# stm32f4stampV1_2.net
KiCad netlist of a schematic drawn in EAGLE
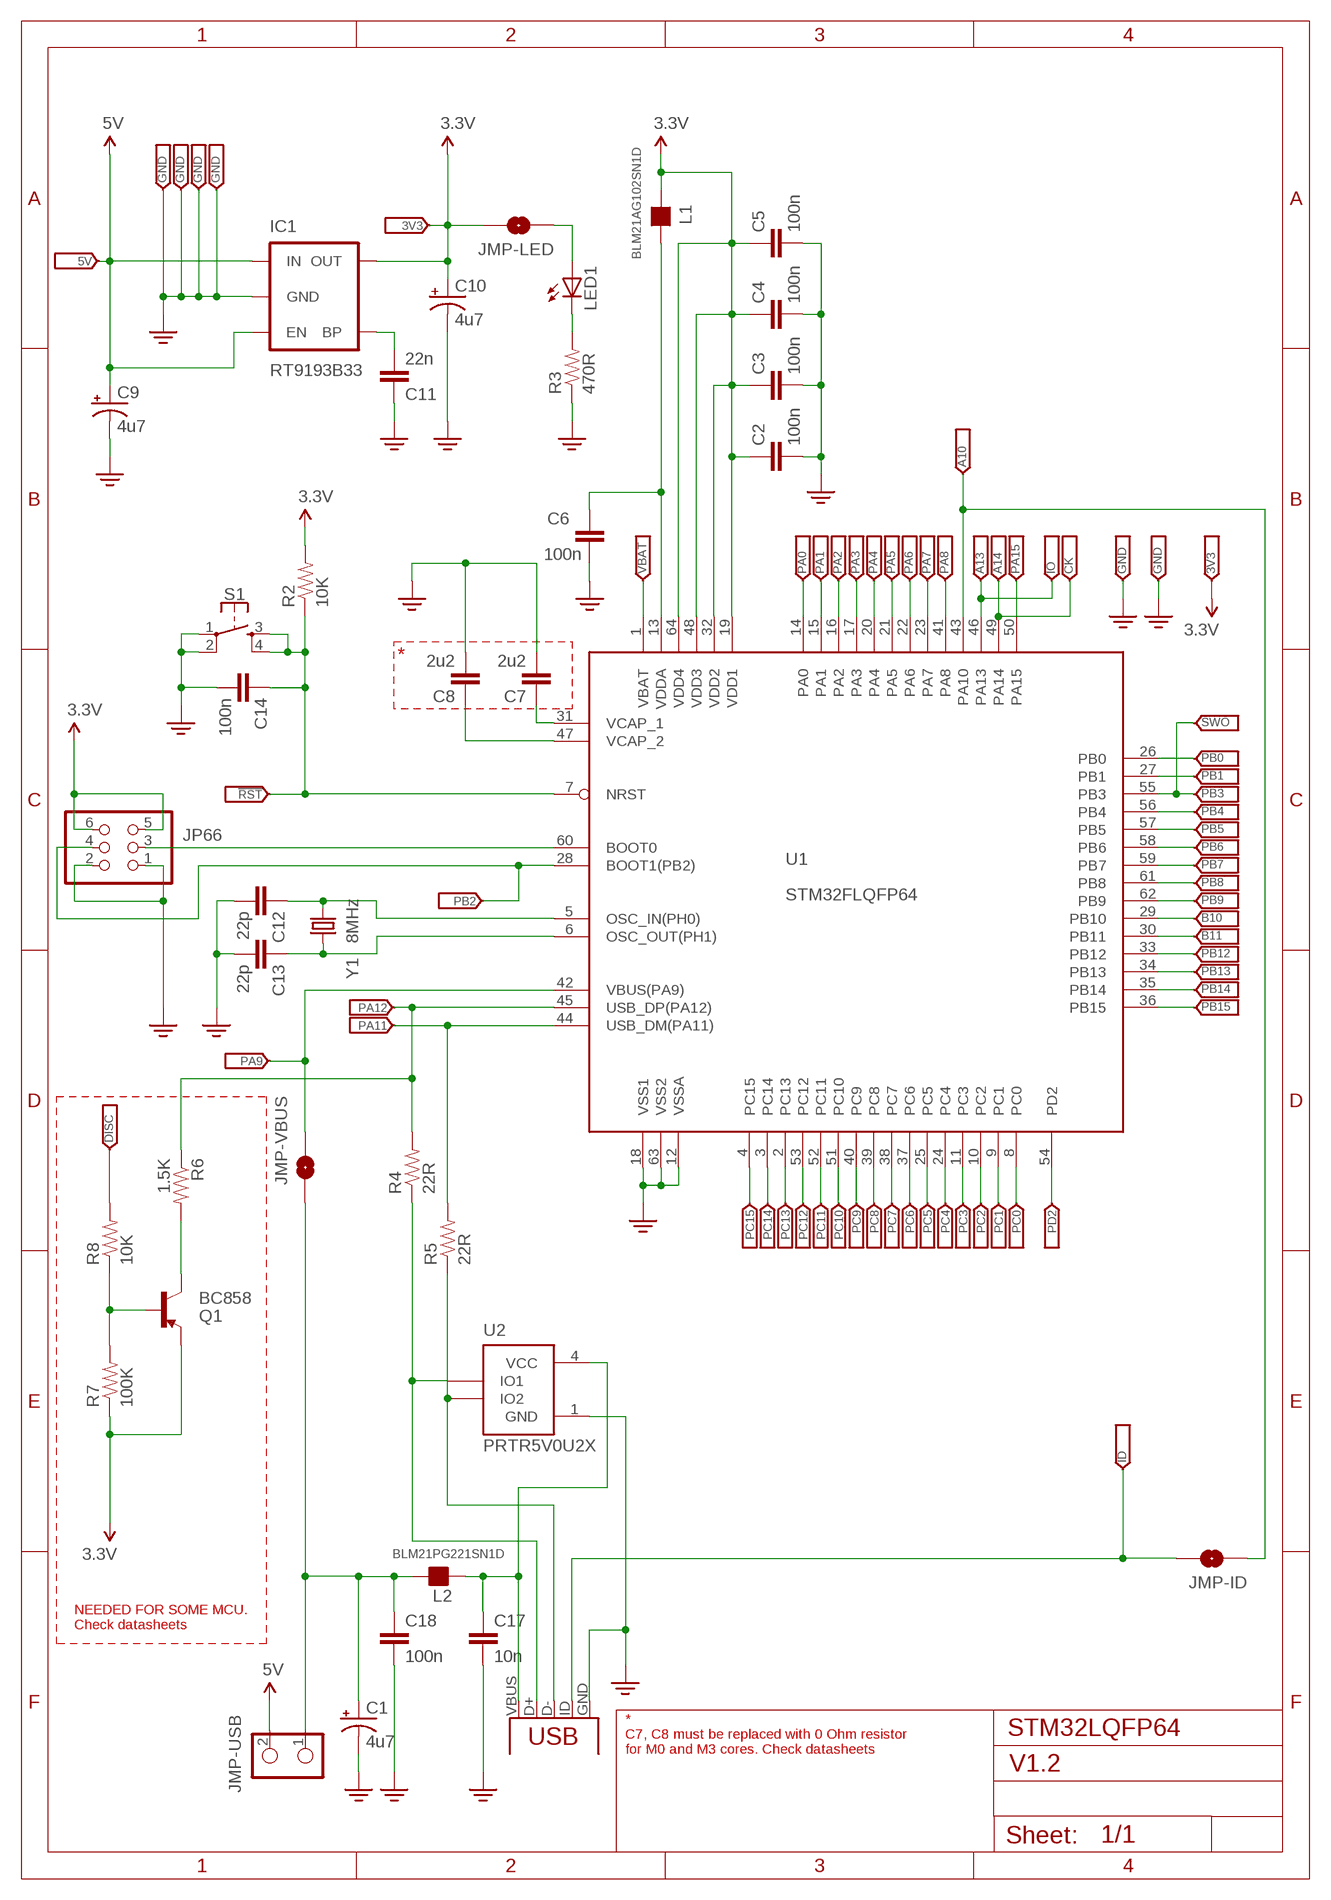
[diagram p0: schematic, sheet 1]

(export (version "E")
  (design (tool "Eeschema 10.0.6"))
  (components
    (comp (ref "C1")
      (value "4u7")
      (footprint "eagle-import:EIA3216-KIT")
      (libsource (lib "eagle-import") (part "CAP_POL1206-KIT"))
    )
    (comp (ref "C2")
      (value "100n")
      (footprint "eagle-import:0805")
      (libsource (lib "eagle-import") (part "CAP0805"))
    )
    (comp (ref "C3")
      (value "100n")
      (footprint "eagle-import:0805")
      (libsource (lib "eagle-import") (part "CAP0805"))
    )
    (comp (ref "C4")
      (value "100n")
      (footprint "eagle-import:0805")
      (libsource (lib "eagle-import") (part "CAP0805"))
    )
    (comp (ref "C5")
      (value "100n")
      (footprint "eagle-import:0805")
      (libsource (lib "eagle-import") (part "CAP0805"))
    )
    (comp (ref "C6")
      (value "100n")
      (footprint "eagle-import:0805")
      (libsource (lib "eagle-import") (part "CAP0805"))
    )
    (comp (ref "C7")
      (value "2u2")
      (footprint "eagle-import:0805")
      (libsource (lib "eagle-import") (part "CAP0805"))
    )
    (comp (ref "C8")
      (value "2u2")
      (footprint "eagle-import:0805")
      (libsource (lib "eagle-import") (part "CAP0805"))
    )
    (comp (ref "C9")
      (value "4u7")
      (footprint "eagle-import:EIA3216-KIT")
      (libsource (lib "eagle-import") (part "CAP_POL1206-KIT"))
    )
    (comp (ref "C10")
      (value "4u7")
      (footprint "eagle-import:EIA3216-KIT")
      (libsource (lib "eagle-import") (part "CAP_POL1206-KIT"))
    )
    (comp (ref "C11")
      (value "22n")
      (footprint "eagle-import:0805")
      (libsource (lib "eagle-import") (part "CAP0805"))
    )
    (comp (ref "C12")
      (value "22p")
      (footprint "eagle-import:0805")
      (libsource (lib "eagle-import") (part "CAP0805"))
    )
    (comp (ref "C13")
      (value "22p")
      (footprint "eagle-import:0805")
      (libsource (lib "eagle-import") (part "CAP0805"))
    )
    (comp (ref "C14")
      (value "100n")
      (footprint "eagle-import:0805")
      (libsource (lib "eagle-import") (part "CAP0805"))
    )
    (comp (ref "C17")
      (value "10n")
      (footprint "eagle-import:0805")
      (libsource (lib "eagle-import") (part "CAP0805"))
    )
    (comp (ref "C18")
      (value "100n")
      (footprint "eagle-import:0805")
      (libsource (lib "eagle-import") (part "CAP0805"))
    )
    (comp (ref "IC1")
      (value "RT9193B33")
      (footprint "eagle-import:SOT23-5")
      (libsource (lib "eagle-import") (part "V_REG_LDOSMD"))
    )
    (comp (ref "JMP-ID")
      (value "SOLDERJUMPERNO")
      (footprint "eagle-import:SJ_2S-NO")
      (libsource (lib "eagle-import") (part "SOLDERJUMPERNO"))
    )
    (comp (ref "JMP-LED")
      (value "SOLDERJUMPERNO")
      (footprint "eagle-import:SJ_2S-NO")
      (libsource (lib "eagle-import") (part "SOLDERJUMPERNO"))
    )
    (comp (ref "JMP-USB")
      (value "JUMPER-2PTH")
      (footprint "eagle-import:1X02")
      (libsource (lib "eagle-import") (part "JUMPER-2PTH"))
    )
    (comp (ref "JMP-VBUS")
      (value "SOLDERJUMPERNO")
      (footprint "eagle-import:SJ_2S-NO")
      (libsource (lib "eagle-import") (part "SOLDERJUMPERNO"))
    )
    (comp (ref "JP1")
      (value "PA12")
      (footprint "eagle-import:1X1-HEADER-HOLE")
      (libsource (lib "eagle-import") (part "HEADERHOLE-HEADERHOLE"))
    )
    (comp (ref "JP2")
      (value "5V")
      (footprint "eagle-import:1X1-HEADER-HOLE")
      (libsource (lib "eagle-import") (part "HEADERHOLE-HEADERHOLE"))
    )
    (comp (ref "JP3")
      (value "GND")
      (footprint "eagle-import:1X1-HEADER-HOLE")
      (libsource (lib "eagle-import") (part "HEADERHOLE-HEADERHOLE"))
    )
    (comp (ref "JP4")
      (value "3V3")
      (footprint "eagle-import:1X1-HEADER-HOLE")
      (libsource (lib "eagle-import") (part "HEADERHOLE-HEADERHOLE"))
    )
    (comp (ref "JP5")
      (value "DISC")
      (footprint "eagle-import:1X1-HEADER-HOLE")
      (libsource (lib "eagle-import") (part "HEADERHOLE-HEADERHOLE"))
    )
    (comp (ref "JP6")
      (value "GND")
      (footprint "eagle-import:1X1-HEADER-HOLE")
      (libsource (lib "eagle-import") (part "HEADERHOLE-HEADERHOLE"))
    )
    (comp (ref "JP7")
      (value "GND")
      (footprint "eagle-import:1X1-HEADER-HOLE")
      (libsource (lib "eagle-import") (part "HEADERHOLE-HEADERHOLE"))
    )
    (comp (ref "JP8")
      (value "PB8")
      (footprint "eagle-import:1X1-HEADER-HOLE")
      (libsource (lib "eagle-import") (part "HEADERHOLE-HEADERHOLE"))
    )
    (comp (ref "JP9")
      (value "A10")
      (footprint "eagle-import:1X1-HEADER-HOLE")
      (libsource (lib "eagle-import") (part "HEADERHOLE-HEADERHOLE"))
    )
    (comp (ref "JP10")
      (value "PA8")
      (footprint "eagle-import:1X1-HEADER-HOLE")
      (libsource (lib "eagle-import") (part "HEADERHOLE-HEADERHOLE"))
    )
    (comp (ref "JP11")
      (value "A13")
      (footprint "eagle-import:1X1-HEADER-HOLE")
      (libsource (lib "eagle-import") (part "HEADERHOLE-HEADERHOLE"))
    )
    (comp (ref "JP12")
      (value "PC9")
      (footprint "eagle-import:1X1-HEADER-HOLE")
      (libsource (lib "eagle-import") (part "HEADERHOLE-HEADERHOLE"))
    )
    (comp (ref "JP13")
      (value "PC15")
      (footprint "eagle-import:1X1-HEADER-HOLE")
      (libsource (lib "eagle-import") (part "HEADERHOLE-HEADERHOLE"))
    )
    (comp (ref "JP14")
      (value "PC14")
      (footprint "eagle-import:1X1-HEADER-HOLE")
      (libsource (lib "eagle-import") (part "HEADERHOLE-HEADERHOLE"))
    )
    (comp (ref "JP15")
      (value "PC13")
      (footprint "eagle-import:1X1-HEADER-HOLE")
      (libsource (lib "eagle-import") (part "HEADERHOLE-HEADERHOLE"))
    )
    (comp (ref "JP16")
      (value "PC12")
      (footprint "eagle-import:1X1-HEADER-HOLE")
      (libsource (lib "eagle-import") (part "HEADERHOLE-HEADERHOLE"))
    )
    (comp (ref "JP17")
      (value "PC11")
      (footprint "eagle-import:1X1-HEADER-HOLE")
      (libsource (lib "eagle-import") (part "HEADERHOLE-HEADERHOLE"))
    )
    (comp (ref "JP18")
      (value "PC10")
      (footprint "eagle-import:1X1-HEADER-HOLE")
      (libsource (lib "eagle-import") (part "HEADERHOLE-HEADERHOLE"))
    )
    (comp (ref "JP19")
      (value "PC8")
      (footprint "eagle-import:1X1-HEADER-HOLE")
      (libsource (lib "eagle-import") (part "HEADERHOLE-HEADERHOLE"))
    )
    (comp (ref "JP20")
      (value "PC7")
      (footprint "eagle-import:1X1-HEADER-HOLE")
      (libsource (lib "eagle-import") (part "HEADERHOLE-HEADERHOLE"))
    )
    (comp (ref "JP21")
      (value "PC6")
      (footprint "eagle-import:1X1-HEADER-HOLE")
      (libsource (lib "eagle-import") (part "HEADERHOLE-HEADERHOLE"))
    )
    (comp (ref "JP22")
      (value "PC5")
      (footprint "eagle-import:1X1-HEADER-HOLE")
      (libsource (lib "eagle-import") (part "HEADERHOLE-HEADERHOLE"))
    )
    (comp (ref "JP23")
      (value "PC4")
      (footprint "eagle-import:1X1-HEADER-HOLE")
      (libsource (lib "eagle-import") (part "HEADERHOLE-HEADERHOLE"))
    )
    (comp (ref "JP24")
      (value "PC3")
      (footprint "eagle-import:1X1-HEADER-HOLE")
      (libsource (lib "eagle-import") (part "HEADERHOLE-HEADERHOLE"))
    )
    (comp (ref "JP25")
      (value "PC2")
      (footprint "eagle-import:1X1-HEADER-HOLE")
      (libsource (lib "eagle-import") (part "HEADERHOLE-HEADERHOLE"))
    )
    (comp (ref "JP26")
      (value "PC1")
      (footprint "eagle-import:1X1-HEADER-HOLE")
      (libsource (lib "eagle-import") (part "HEADERHOLE-HEADERHOLE"))
    )
    (comp (ref "JP27")
      (value "PC0")
      (footprint "eagle-import:1X1-HEADER-HOLE")
      (libsource (lib "eagle-import") (part "HEADERHOLE-HEADERHOLE"))
    )
    (comp (ref "JP28")
      (value "PD2")
      (footprint "eagle-import:1X1-HEADER-HOLE")
      (libsource (lib "eagle-import") (part "HEADERHOLE-HEADERHOLE"))
    )
    (comp (ref "JP29")
      (value "PA0")
      (footprint "eagle-import:1X1-HEADER-HOLE")
      (libsource (lib "eagle-import") (part "HEADERHOLE-HEADERHOLE"))
    )
    (comp (ref "JP30")
      (value "PA1")
      (footprint "eagle-import:1X1-HEADER-HOLE")
      (libsource (lib "eagle-import") (part "HEADERHOLE-HEADERHOLE"))
    )
    (comp (ref "JP31")
      (value "PA2")
      (footprint "eagle-import:1X1-HEADER-HOLE")
      (libsource (lib "eagle-import") (part "HEADERHOLE-HEADERHOLE"))
    )
    (comp (ref "JP32")
      (value "PA3")
      (footprint "eagle-import:1X1-HEADER-HOLE")
      (libsource (lib "eagle-import") (part "HEADERHOLE-HEADERHOLE"))
    )
    (comp (ref "JP33")
      (value "PA4")
      (footprint "eagle-import:1X1-HEADER-HOLE")
      (libsource (lib "eagle-import") (part "HEADERHOLE-HEADERHOLE"))
    )
    (comp (ref "JP34")
      (value "PA5")
      (footprint "eagle-import:1X1-HEADER-HOLE")
      (libsource (lib "eagle-import") (part "HEADERHOLE-HEADERHOLE"))
    )
    (comp (ref "JP35")
      (value "PA6")
      (footprint "eagle-import:1X1-HEADER-HOLE")
      (libsource (lib "eagle-import") (part "HEADERHOLE-HEADERHOLE"))
    )
    (comp (ref "JP36")
      (value "PA7")
      (footprint "eagle-import:1X1-HEADER-HOLE")
      (libsource (lib "eagle-import") (part "HEADERHOLE-HEADERHOLE"))
    )
    (comp (ref "JP37")
      (value "A14")
      (footprint "eagle-import:1X1-HEADER-HOLE")
      (libsource (lib "eagle-import") (part "HEADERHOLE-HEADERHOLE"))
    )
    (comp (ref "JP38")
      (value "PA15")
      (footprint "eagle-import:1X1-HEADER-HOLE")
      (libsource (lib "eagle-import") (part "HEADERHOLE-HEADERHOLE"))
    )
    (comp (ref "JP39")
      (value "PB0")
      (footprint "eagle-import:1X1-HEADER-HOLE")
      (libsource (lib "eagle-import") (part "HEADERHOLE-HEADERHOLE"))
    )
    (comp (ref "JP40")
      (value "PB1")
      (footprint "eagle-import:1X1-HEADER-HOLE")
      (libsource (lib "eagle-import") (part "HEADERHOLE-HEADERHOLE"))
    )
    (comp (ref "JP41")
      (value "PB3")
      (footprint "eagle-import:1X1-HEADER-HOLE")
      (libsource (lib "eagle-import") (part "HEADERHOLE-HEADERHOLE"))
    )
    (comp (ref "JP42")
      (value "PB4")
      (footprint "eagle-import:1X1-HEADER-HOLE")
      (libsource (lib "eagle-import") (part "HEADERHOLE-HEADERHOLE"))
    )
    (comp (ref "JP43")
      (value "PB5")
      (footprint "eagle-import:1X1-HEADER-HOLE")
      (libsource (lib "eagle-import") (part "HEADERHOLE-HEADERHOLE"))
    )
    (comp (ref "JP44")
      (value "PB6")
      (footprint "eagle-import:1X1-HEADER-HOLE")
      (libsource (lib "eagle-import") (part "HEADERHOLE-HEADERHOLE"))
    )
    (comp (ref "JP45")
      (value "PB7")
      (footprint "eagle-import:1X1-HEADER-HOLE")
      (libsource (lib "eagle-import") (part "HEADERHOLE-HEADERHOLE"))
    )
    (comp (ref "JP46")
      (value "PB9")
      (footprint "eagle-import:1X1-HEADER-HOLE")
      (libsource (lib "eagle-import") (part "HEADERHOLE-HEADERHOLE"))
    )
    (comp (ref "JP47")
      (value "B10")
      (footprint "eagle-import:1X1-HEADER-HOLE")
      (libsource (lib "eagle-import") (part "HEADERHOLE-HEADERHOLE"))
    )
    (comp (ref "JP48")
      (value "B11")
      (footprint "eagle-import:1X1-HEADER-HOLE")
      (libsource (lib "eagle-import") (part "HEADERHOLE-HEADERHOLE"))
    )
    (comp (ref "JP49")
      (value "PB12")
      (footprint "eagle-import:1X1-HEADER-HOLE")
      (libsource (lib "eagle-import") (part "HEADERHOLE-HEADERHOLE"))
    )
    (comp (ref "JP50")
      (value "PB13")
      (footprint "eagle-import:1X1-HEADER-HOLE")
      (libsource (lib "eagle-import") (part "HEADERHOLE-HEADERHOLE"))
    )
    (comp (ref "JP51")
      (value "PB14")
      (footprint "eagle-import:1X1-HEADER-HOLE")
      (libsource (lib "eagle-import") (part "HEADERHOLE-HEADERHOLE"))
    )
    (comp (ref "JP52")
      (value "PB15")
      (footprint "eagle-import:1X1-HEADER-HOLE")
      (libsource (lib "eagle-import") (part "HEADERHOLE-HEADERHOLE"))
    )
    (comp (ref "JP53")
      (value "VBAT")
      (footprint "eagle-import:1X1-HEADER-HOLE")
      (libsource (lib "eagle-import") (part "HEADERHOLE-HEADERHOLE"))
    )
    (comp (ref "JP54")
      (value "!RST")
      (footprint "eagle-import:1X1-HEADER-HOLE")
      (libsource (lib "eagle-import") (part "HEADERHOLE-HEADERHOLE"))
    )
    (comp (ref "JP55")
      (value "GND")
      (footprint "eagle-import:1X1-HEADER-HOLE")
      (libsource (lib "eagle-import") (part "HEADERHOLE-HEADERHOLE"))
    )
    (comp (ref "JP56")
      (value "ID")
      (footprint "eagle-import:1X1-HEADER-HOLE")
      (libsource (lib "eagle-import") (part "HEADERHOLE-HEADERHOLE"))
    )
    (comp (ref "JP57")
      (value "PB2")
      (footprint "eagle-import:1X1-HEADER-HOLE")
      (libsource (lib "eagle-import") (part "HEADERHOLE-HEADERHOLE"))
    )
    (comp (ref "JP58")
      (value "PA11")
      (footprint "eagle-import:1X1-HEADER-HOLE")
      (libsource (lib "eagle-import") (part "HEADERHOLE-HEADERHOLE"))
    )
    (comp (ref "JP59")
      (value "IO")
      (footprint "eagle-import:1X1-HEADER-HOLE")
      (libsource (lib "eagle-import") (part "HEADERHOLE-HEADERHOLE"))
    )
    (comp (ref "JP60")
      (value "CK")
      (footprint "eagle-import:1X1-HEADER-HOLE")
      (libsource (lib "eagle-import") (part "HEADERHOLE-HEADERHOLE"))
    )
    (comp (ref "JP61")
      (value "SWO")
      (footprint "eagle-import:1X1-HEADER-HOLE")
      (libsource (lib "eagle-import") (part "HEADERHOLE-HEADERHOLE"))
    )
    (comp (ref "JP62")
      (value "GND")
      (footprint "eagle-import:1X1-HEADER-HOLE")
      (libsource (lib "eagle-import") (part "HEADERHOLE-HEADERHOLE"))
    )
    (comp (ref "JP63")
      (value "3V3")
      (footprint "eagle-import:1X1-HEADER-HOLE")
      (libsource (lib "eagle-import") (part "HEADERHOLE-HEADERHOLE"))
    )
    (comp (ref "JP64")
      (value "PA9")
      (footprint "eagle-import:1X1-HEADER-HOLE")
      (libsource (lib "eagle-import") (part "HEADERHOLE-HEADERHOLE"))
    )
    (comp (ref "JP65")
      (value "GND")
      (footprint "eagle-import:1X1-HEADER-HOLE")
      (libsource (lib "eagle-import") (part "HEADERHOLE-HEADERHOLE"))
    )
    (comp (ref "JP66")
      (value "PINHD-2X3")
      (footprint "eagle-import:2X03")
      (libsource (lib "eagle-import") (part "PINHD-2X3"))
    )
    (comp (ref "L1")
      (value "BLM21AG102SN1D")
      (footprint "eagle-import:L0805")
      (libsource (lib "eagle-import") (part "FB_0805"))
    )
    (comp (ref "L2")
      (value "BLM21PG221SN1D")
      (footprint "eagle-import:L0805")
      (libsource (lib "eagle-import") (part "FB_0805"))
    )
    (comp (ref "LED1")
      (value "LEDSML0805")
      (footprint "eagle-import:SML0805")
      (libsource (lib "eagle-import") (part "LEDSML0805"))
    )
    (comp (ref "Q1")
      (value "BC858")
      (footprint "eagle-import:SOT23-3")
      (libsource (lib "eagle-import") (part "TRANSISTOR_PNPSMD"))
    )
    (comp (ref "R2")
      (value "10K")
      (footprint "eagle-import:0805")
      (libsource (lib "eagle-import") (part "RESISTOR0805-RES"))
    )
    (comp (ref "R3")
      (value "470R")
      (footprint "eagle-import:0805")
      (libsource (lib "eagle-import") (part "RESISTOR0805-RES"))
    )
    (comp (ref "R4")
      (value "22R")
      (footprint "eagle-import:0805")
      (libsource (lib "eagle-import") (part "RESISTOR0805-RES"))
    )
    (comp (ref "R5")
      (value "22R")
      (footprint "eagle-import:0805")
      (libsource (lib "eagle-import") (part "RESISTOR0805-RES"))
    )
    (comp (ref "R6")
      (value "1.5K")
      (footprint "eagle-import:0805")
      (libsource (lib "eagle-import") (part "RESISTOR0805-RES"))
    )
    (comp (ref "R7")
      (value "100K")
      (footprint "eagle-import:0805")
      (libsource (lib "eagle-import") (part "RESISTOR0805-RES"))
    )
    (comp (ref "R8")
      (value "10K")
      (footprint "eagle-import:0805")
      (libsource (lib "eagle-import") (part "RESISTOR0805-RES"))
    )
    (comp (ref "S1")
      (value "MOMENTARY-SWITCH-SPST-2-SMD-5.2MM")
      (footprint "eagle-import:TACTILE_SWITCH_SMD_5.2MM")
      (libsource (lib "eagle-import") (part "MOMENTARY-SWITCH-SPST-2-SMD-5.2MM"))
    )
    (comp (ref "U1")
      (value "STM32FLQFP64")
      (footprint "eagle-import:LQFP64")
      (libsource (lib "eagle-import") (part "STM32F405RGT"))
    )
    (comp (ref "U2")
      (value "PRTR5V0U2X")
      (footprint "eagle-import:SOT-143B")
      (fields
        (field (name "MANUFACTURER") "NXP Semiconductors")
        (field (name "PART_NUMBER") "PRTR5V0U2X,215")
      )
      (libsource (lib "eagle-import") (part "PRTR5V0U2X?"))
    )
    (comp (ref "USB")
      (value "USB-MICROB-SMD")
      (footprint "eagle-import:USB-MICROB-SMD")
      (libsource (lib "eagle-import") (part "USB-MICROB-SMD"))
    )
    (comp (ref "Y1")
      (value "8MHz")
      (footprint "eagle-import:CRYSTAL-SMD-5X3")
      (libsource (lib "eagle-import") (part "CRYSTAL5X3"))
    )
  )
  (nets
    (net (code "1") (name "3.3V") (class "Default")
      (node (ref "C10") (pin "A") (pinfunction "+_A") (pintype "passive"))
      (node (ref "C2") (pin "1") (pinfunction "1_1") (pintype "passive"))
      (node (ref "C3") (pin "1") (pinfunction "1_1") (pintype "passive"))
      (node (ref "C4") (pin "1") (pinfunction "1_1") (pintype "passive"))
      (node (ref "C5") (pin "1") (pinfunction "1_1") (pintype "passive"))
      (node (ref "IC1") (pin "5") (pinfunction "OUT_5") (pintype "passive"))
      (node (ref "JMP-LED") (pin "2") (pinfunction "2_2") (pintype "passive"))
      (node (ref "JP4") (pin "1") (pinfunction "P$1_1") (pintype "bidirectional"))
      (node (ref "JP63") (pin "1") (pinfunction "P$1_1") (pintype "bidirectional"))
      (node (ref "JP66") (pin "5") (pinfunction "5_5") (pintype "passive"))
      (node (ref "JP66") (pin "6") (pinfunction "6_6") (pintype "passive"))
      (node (ref "L1") (pin "2") (pinfunction "2_2") (pintype "passive"))
      (node (ref "Q1") (pin "2") (pinfunction "E_2") (pintype "passive"))
      (node (ref "R2") (pin "2") (pinfunction "2_2") (pintype "passive"))
      (node (ref "R7") (pin "1") (pinfunction "1_1") (pintype "passive"))
      (node (ref "U1") (pin "19") (pinfunction "VDD1_19") (pintype "power_in"))
      (node (ref "U1") (pin "32") (pinfunction "VDD2_32") (pintype "power_in"))
      (node (ref "U1") (pin "48") (pinfunction "VDD3_48") (pintype "power_in"))
      (node (ref "U1") (pin "64") (pinfunction "VDD4_64") (pintype "power_in"))
    )
    (net (code "2") (name "5V") (class "Default")
      (node (ref "C9") (pin "A") (pinfunction "+_A") (pintype "passive"))
      (node (ref "IC1") (pin "1") (pinfunction "IN_1") (pintype "input"))
      (node (ref "IC1") (pin "3") (pinfunction "EN_3") (pintype "input"))
      (node (ref "JMP-USB") (pin "2") (pinfunction "2_2") (pintype "passive"))
      (node (ref "JP2") (pin "1") (pinfunction "P$1_1") (pintype "bidirectional"))
    )
    (net (code "3") (name "GND") (class "Default")
      (node (ref "C1") (pin "C") (pinfunction "-_C") (pintype "passive"))
      (node (ref "C10") (pin "C") (pinfunction "-_C") (pintype "passive"))
      (node (ref "C11") (pin "1") (pinfunction "1_1") (pintype "passive"))
      (node (ref "C12") (pin "2") (pinfunction "2_2") (pintype "passive"))
      (node (ref "C13") (pin "2") (pinfunction "2_2") (pintype "passive"))
      (node (ref "C14") (pin "2") (pinfunction "2_2") (pintype "passive"))
      (node (ref "C17") (pin "2") (pinfunction "2_2") (pintype "passive"))
      (node (ref "C18") (pin "2") (pinfunction "2_2") (pintype "passive"))
      (node (ref "C2") (pin "2") (pinfunction "2_2") (pintype "passive"))
      (node (ref "C3") (pin "2") (pinfunction "2_2") (pintype "passive"))
      (node (ref "C4") (pin "2") (pinfunction "2_2") (pintype "passive"))
      (node (ref "C5") (pin "2") (pinfunction "2_2") (pintype "passive"))
      (node (ref "C6") (pin "2") (pinfunction "2_2") (pintype "passive"))
      (node (ref "C7") (pin "2") (pinfunction "2_2") (pintype "passive"))
      (node (ref "C8") (pin "2") (pinfunction "2_2") (pintype "passive"))
      (node (ref "C9") (pin "C") (pinfunction "-_C") (pintype "passive"))
      (node (ref "IC1") (pin "2") (pinfunction "GND_2") (pintype "input"))
      (node (ref "JP3") (pin "1") (pinfunction "P$1_1") (pintype "bidirectional"))
      (node (ref "JP55") (pin "1") (pinfunction "P$1_1") (pintype "bidirectional"))
      (node (ref "JP6") (pin "1") (pinfunction "P$1_1") (pintype "bidirectional"))
      (node (ref "JP62") (pin "1") (pinfunction "P$1_1") (pintype "bidirectional"))
      (node (ref "JP65") (pin "1") (pinfunction "P$1_1") (pintype "bidirectional"))
      (node (ref "JP66") (pin "1") (pinfunction "1_1") (pintype "passive"))
      (node (ref "JP66") (pin "2") (pinfunction "2_2") (pintype "passive"))
      (node (ref "JP7") (pin "1") (pinfunction "P$1_1") (pintype "bidirectional"))
      (node (ref "R3") (pin "1") (pinfunction "1_1") (pintype "passive"))
      (node (ref "S1") (pin "1") (pinfunction "1_1") (pintype "passive"))
      (node (ref "S1") (pin "2") (pinfunction "2_2") (pintype "passive"))
      (node (ref "U1") (pin "12") (pinfunction "VSSA_12") (pintype "power_in"))
      (node (ref "U1") (pin "18") (pinfunction "VSS1_18") (pintype "power_in"))
      (node (ref "U1") (pin "63") (pinfunction "VSS2_63") (pintype "power_in"))
      (node (ref "U2") (pin "1") (pinfunction "GND_1") (pintype "bidirectional"))
      (node (ref "USB") (pin "GND") (pinfunction "GND_GND") (pintype "bidirectional"))
      (node (ref "USB") (pin "MT1") (pinfunction "P$1_MT1") (pintype "bidirectional"))
      (node (ref "USB") (pin "MT2") (pinfunction "P$1_MT2") (pintype "bidirectional"))
      (node (ref "USB") (pin "MT3") (pinfunction "P$1_MT3") (pintype "bidirectional"))
      (node (ref "USB") (pin "MT4") (pinfunction "P$1_MT4") (pintype "bidirectional"))
    )
    (net (code "4") (name "Net-(C1-+)") (class "Default")
      (node (ref "C1") (pin "A") (pinfunction "+_A") (pintype "passive"))
      (node (ref "C18") (pin "1") (pinfunction "1_1") (pintype "passive"))
      (node (ref "JMP-USB") (pin "1") (pinfunction "1_1") (pintype "passive"))
      (node (ref "JMP-VBUS") (pin "1") (pinfunction "1_1") (pintype "passive"))
      (node (ref "L2") (pin "2") (pinfunction "2_2") (pintype "passive"))
    )
    (net (code "5") (name "Net-(IC1-BP)") (class "Default")
      (node (ref "C11") (pin "2") (pinfunction "2_2") (pintype "passive"))
      (node (ref "IC1") (pin "4") (pinfunction "BP_4") (pintype "input"))
    )
    (net (code "6") (name "Net-(JMP-LED-Pad1)") (class "Default")
      (node (ref "JMP-LED") (pin "1") (pinfunction "1_1") (pintype "passive"))
      (node (ref "LED1") (pin "A") (pinfunction "A_A") (pintype "passive"))
    )
    (net (code "7") (name "Net-(JP1-P$1)") (class "Default")
      (node (ref "JP1") (pin "1") (pinfunction "P$1_1") (pintype "bidirectional"))
      (node (ref "R4") (pin "2") (pinfunction "2_2") (pintype "passive"))
      (node (ref "R6") (pin "1") (pinfunction "1_1") (pintype "passive"))
      (node (ref "U1") (pin "45") (pinfunction "USB_DP(PA12)_45") (pintype "bidirectional"))
    )
    (net (code "8") (name "Net-(JP5-P$1)") (class "Default")
      (node (ref "JP5") (pin "1") (pinfunction "P$1_1") (pintype "bidirectional"))
      (node (ref "R8") (pin "2") (pinfunction "2_2") (pintype "passive"))
    )
    (net (code "9") (name "Net-(JP8-P$1)") (class "Default")
      (node (ref "JP8") (pin "1") (pinfunction "P$1_1") (pintype "bidirectional"))
      (node (ref "U1") (pin "61") (pinfunction "PB8_61") (pintype "bidirectional"))
    )
    (net (code "10") (name "Net-(JP9-P$1)") (class "Default")
      (node (ref "JMP-ID") (pin "1") (pinfunction "1_1") (pintype "passive"))
      (node (ref "JP9") (pin "1") (pinfunction "P$1_1") (pintype "bidirectional"))
      (node (ref "U1") (pin "43") (pinfunction "PA10_43") (pintype "bidirectional"))
    )
    (net (code "11") (name "Net-(JP10-P$1)") (class "Default")
      (node (ref "JP10") (pin "1") (pinfunction "P$1_1") (pintype "bidirectional"))
      (node (ref "U1") (pin "41") (pinfunction "PA8_41") (pintype "bidirectional"))
    )
    (net (code "12") (name "Net-(JP11-P$1)") (class "Default")
      (node (ref "JP11") (pin "1") (pinfunction "P$1_1") (pintype "bidirectional"))
      (node (ref "JP59") (pin "1") (pinfunction "P$1_1") (pintype "bidirectional"))
      (node (ref "U1") (pin "46") (pinfunction "PA13_46") (pintype "bidirectional"))
    )
    (net (code "13") (name "Net-(JP12-P$1)") (class "Default")
      (node (ref "JP12") (pin "1") (pinfunction "P$1_1") (pintype "bidirectional"))
      (node (ref "U1") (pin "40") (pinfunction "PC9_40") (pintype "bidirectional"))
    )
    (net (code "14") (name "Net-(JP13-P$1)") (class "Default")
      (node (ref "JP13") (pin "1") (pinfunction "P$1_1") (pintype "bidirectional"))
      (node (ref "U1") (pin "4") (pinfunction "PC15_4") (pintype "bidirectional"))
    )
    (net (code "15") (name "Net-(JP14-P$1)") (class "Default")
      (node (ref "JP14") (pin "1") (pinfunction "P$1_1") (pintype "bidirectional"))
      (node (ref "U1") (pin "3") (pinfunction "PC14_3") (pintype "bidirectional"))
    )
    (net (code "16") (name "Net-(JP15-P$1)") (class "Default")
      (node (ref "JP15") (pin "1") (pinfunction "P$1_1") (pintype "bidirectional"))
      (node (ref "U1") (pin "2") (pinfunction "PC13_2") (pintype "bidirectional"))
    )
    (net (code "17") (name "Net-(JP16-P$1)") (class "Default")
      (node (ref "JP16") (pin "1") (pinfunction "P$1_1") (pintype "bidirectional"))
      (node (ref "U1") (pin "53") (pinfunction "PC12_53") (pintype "bidirectional"))
    )
    (net (code "18") (name "Net-(JP17-P$1)") (class "Default")
      (node (ref "JP17") (pin "1") (pinfunction "P$1_1") (pintype "bidirectional"))
      (node (ref "U1") (pin "52") (pinfunction "PC11_52") (pintype "bidirectional"))
    )
    (net (code "19") (name "Net-(JP18-P$1)") (class "Default")
      (node (ref "JP18") (pin "1") (pinfunction "P$1_1") (pintype "bidirectional"))
      (node (ref "U1") (pin "51") (pinfunction "PC10_51") (pintype "bidirectional"))
    )
    (net (code "20") (name "Net-(JP19-P$1)") (class "Default")
      (node (ref "JP19") (pin "1") (pinfunction "P$1_1") (pintype "bidirectional"))
      (node (ref "U1") (pin "39") (pinfunction "PC8_39") (pintype "bidirectional"))
    )
    (net (code "21") (name "Net-(JP20-P$1)") (class "Default")
      (node (ref "JP20") (pin "1") (pinfunction "P$1_1") (pintype "bidirectional"))
      (node (ref "U1") (pin "38") (pinfunction "PC7_38") (pintype "bidirectional"))
    )
    (net (code "22") (name "Net-(JP21-P$1)") (class "Default")
      (node (ref "JP21") (pin "1") (pinfunction "P$1_1") (pintype "bidirectional"))
      (node (ref "U1") (pin "37") (pinfunction "PC6_37") (pintype "bidirectional"))
    )
    (net (code "23") (name "Net-(JP22-P$1)") (class "Default")
      (node (ref "JP22") (pin "1") (pinfunction "P$1_1") (pintype "bidirectional"))
      (node (ref "U1") (pin "25") (pinfunction "PC5_25") (pintype "bidirectional"))
    )
    (net (code "24") (name "Net-(JP23-P$1)") (class "Default")
      (node (ref "JP23") (pin "1") (pinfunction "P$1_1") (pintype "bidirectional"))
      (node (ref "U1") (pin "24") (pinfunction "PC4_24") (pintype "bidirectional"))
    )
    (net (code "25") (name "Net-(JP24-P$1)") (class "Default")
      (node (ref "JP24") (pin "1") (pinfunction "P$1_1") (pintype "bidirectional"))
      (node (ref "U1") (pin "11") (pinfunction "PC3_11") (pintype "bidirectional"))
    )
    (net (code "26") (name "Net-(JP25-P$1)") (class "Default")
      (node (ref "JP25") (pin "1") (pinfunction "P$1_1") (pintype "bidirectional"))
      (node (ref "U1") (pin "10") (pinfunction "PC2_10") (pintype "bidirectional"))
    )
    (net (code "27") (name "Net-(JP26-P$1)") (class "Default")
      (node (ref "JP26") (pin "1") (pinfunction "P$1_1") (pintype "bidirectional"))
      (node (ref "U1") (pin "9") (pinfunction "PC1_9") (pintype "bidirectional"))
    )
    (net (code "28") (name "Net-(JP27-P$1)") (class "Default")
      (node (ref "JP27") (pin "1") (pinfunction "P$1_1") (pintype "bidirectional"))
      (node (ref "U1") (pin "8") (pinfunction "PC0_8") (pintype "bidirectional"))
    )
    (net (code "29") (name "Net-(JP28-P$1)") (class "Default")
      (node (ref "JP28") (pin "1") (pinfunction "P$1_1") (pintype "bidirectional"))
      (node (ref "U1") (pin "54") (pinfunction "PD2_54") (pintype "bidirectional"))
    )
    (net (code "30") (name "Net-(JP29-P$1)") (class "Default")
      (node (ref "JP29") (pin "1") (pinfunction "P$1_1") (pintype "bidirectional"))
      (node (ref "U1") (pin "14") (pinfunction "PA0_14") (pintype "bidirectional"))
    )
    (net (code "31") (name "Net-(JP30-P$1)") (class "Default")
      (node (ref "JP30") (pin "1") (pinfunction "P$1_1") (pintype "bidirectional"))
      (node (ref "U1") (pin "15") (pinfunction "PA1_15") (pintype "bidirectional"))
    )
    (net (code "32") (name "Net-(JP31-P$1)") (class "Default")
      (node (ref "JP31") (pin "1") (pinfunction "P$1_1") (pintype "bidirectional"))
      (node (ref "U1") (pin "16") (pinfunction "PA2_16") (pintype "bidirectional"))
    )
    (net (code "33") (name "Net-(JP32-P$1)") (class "Default")
      (node (ref "JP32") (pin "1") (pinfunction "P$1_1") (pintype "bidirectional"))
      (node (ref "U1") (pin "17") (pinfunction "PA3_17") (pintype "bidirectional"))
    )
    (net (code "34") (name "Net-(JP33-P$1)") (class "Default")
      (node (ref "JP33") (pin "1") (pinfunction "P$1_1") (pintype "bidirectional"))
      (node (ref "U1") (pin "20") (pinfunction "PA4_20") (pintype "bidirectional"))
    )
    (net (code "35") (name "Net-(JP34-P$1)") (class "Default")
      (node (ref "JP34") (pin "1") (pinfunction "P$1_1") (pintype "bidirectional"))
      (node (ref "U1") (pin "21") (pinfunction "PA5_21") (pintype "bidirectional"))
    )
    (net (code "36") (name "Net-(JP35-P$1)") (class "Default")
      (node (ref "JP35") (pin "1") (pinfunction "P$1_1") (pintype "bidirectional"))
      (node (ref "U1") (pin "22") (pinfunction "PA6_22") (pintype "bidirectional"))
    )
    (net (code "37") (name "Net-(JP36-P$1)") (class "Default")
      (node (ref "JP36") (pin "1") (pinfunction "P$1_1") (pintype "bidirectional"))
      (node (ref "U1") (pin "23") (pinfunction "PA7_23") (pintype "bidirectional"))
    )
    (net (code "38") (name "Net-(JP37-P$1)") (class "Default")
      (node (ref "JP37") (pin "1") (pinfunction "P$1_1") (pintype "bidirectional"))
      (node (ref "JP60") (pin "1") (pinfunction "P$1_1") (pintype "bidirectional"))
      (node (ref "U1") (pin "49") (pinfunction "PA14_49") (pintype "bidirectional"))
    )
    (net (code "39") (name "Net-(JP38-P$1)") (class "Default")
      (node (ref "JP38") (pin "1") (pinfunction "P$1_1") (pintype "bidirectional"))
      (node (ref "U1") (pin "50") (pinfunction "PA15_50") (pintype "bidirectional"))
    )
    (net (code "40") (name "Net-(JP39-P$1)") (class "Default")
      (node (ref "JP39") (pin "1") (pinfunction "P$1_1") (pintype "bidirectional"))
      (node (ref "U1") (pin "26") (pinfunction "PB0_26") (pintype "bidirectional"))
    )
    (net (code "41") (name "Net-(JP40-P$1)") (class "Default")
      (node (ref "JP40") (pin "1") (pinfunction "P$1_1") (pintype "bidirectional"))
      (node (ref "U1") (pin "27") (pinfunction "PB1_27") (pintype "bidirectional"))
    )
    (net (code "42") (name "Net-(JP41-P$1)") (class "Default")
      (node (ref "JP41") (pin "1") (pinfunction "P$1_1") (pintype "bidirectional"))
      (node (ref "JP61") (pin "1") (pinfunction "P$1_1") (pintype "bidirectional"))
      (node (ref "U1") (pin "55") (pinfunction "PB3_55") (pintype "bidirectional"))
    )
    (net (code "43") (name "Net-(JP42-P$1)") (class "Default")
      (node (ref "JP42") (pin "1") (pinfunction "P$1_1") (pintype "bidirectional"))
      (node (ref "U1") (pin "56") (pinfunction "PB4_56") (pintype "bidirectional"))
    )
    (net (code "44") (name "Net-(JP43-P$1)") (class "Default")
      (node (ref "JP43") (pin "1") (pinfunction "P$1_1") (pintype "bidirectional"))
      (node (ref "U1") (pin "57") (pinfunction "PB5_57") (pintype "bidirectional"))
    )
    (net (code "45") (name "Net-(JP44-P$1)") (class "Default")
      (node (ref "JP44") (pin "1") (pinfunction "P$1_1") (pintype "bidirectional"))
      (node (ref "U1") (pin "58") (pinfunction "PB6_58") (pintype "bidirectional"))
    )
    (net (code "46") (name "Net-(JP45-P$1)") (class "Default")
      (node (ref "JP45") (pin "1") (pinfunction "P$1_1") (pintype "bidirectional"))
      (node (ref "U1") (pin "59") (pinfunction "PB7_59") (pintype "bidirectional"))
    )
    (net (code "47") (name "Net-(JP46-P$1)") (class "Default")
      (node (ref "JP46") (pin "1") (pinfunction "P$1_1") (pintype "bidirectional"))
      (node (ref "U1") (pin "62") (pinfunction "PB9_62") (pintype "bidirectional"))
    )
    (net (code "48") (name "Net-(JP47-P$1)") (class "Default")
      (node (ref "JP47") (pin "1") (pinfunction "P$1_1") (pintype "bidirectional"))
      (node (ref "U1") (pin "29") (pinfunction "PB10_29") (pintype "bidirectional"))
    )
    (net (code "49") (name "Net-(JP48-P$1)") (class "Default")
      (node (ref "JP48") (pin "1") (pinfunction "P$1_1") (pintype "bidirectional"))
      (node (ref "U1") (pin "30") (pinfunction "PB11_30") (pintype "bidirectional"))
    )
    (net (code "50") (name "Net-(JP49-P$1)") (class "Default")
      (node (ref "JP49") (pin "1") (pinfunction "P$1_1") (pintype "bidirectional"))
      (node (ref "U1") (pin "33") (pinfunction "PB12_33") (pintype "bidirectional"))
    )
    (net (code "51") (name "Net-(JP50-P$1)") (class "Default")
      (node (ref "JP50") (pin "1") (pinfunction "P$1_1") (pintype "bidirectional"))
      (node (ref "U1") (pin "34") (pinfunction "PB13_34") (pintype "bidirectional"))
    )
    (net (code "52") (name "Net-(JP51-P$1)") (class "Default")
      (node (ref "JP51") (pin "1") (pinfunction "P$1_1") (pintype "bidirectional"))
      (node (ref "U1") (pin "35") (pinfunction "PB14_35") (pintype "bidirectional"))
    )
    (net (code "53") (name "Net-(JP52-P$1)") (class "Default")
      (node (ref "JP52") (pin "1") (pinfunction "P$1_1") (pintype "bidirectional"))
      (node (ref "U1") (pin "36") (pinfunction "PB15_36") (pintype "bidirectional"))
    )
    (net (code "54") (name "Net-(JP53-P$1)") (class "Default")
      (node (ref "JP53") (pin "1") (pinfunction "P$1_1") (pintype "bidirectional"))
      (node (ref "U1") (pin "1") (pinfunction "VBAT_1") (pintype "power_in"))
    )
    (net (code "55") (name "Net-(JP54-P$1)") (class "Default")
      (node (ref "C14") (pin "1") (pinfunction "1_1") (pintype "passive"))
      (node (ref "JP54") (pin "1") (pinfunction "P$1_1") (pintype "bidirectional"))
      (node (ref "R2") (pin "1") (pinfunction "1_1") (pintype "passive"))
      (node (ref "S1") (pin "3") (pinfunction "3_3") (pintype "passive"))
      (node (ref "S1") (pin "4") (pinfunction "4_4") (pintype "passive"))
      (node (ref "U1") (pin "7") (pinfunction "NRST_7") (pintype "input"))
    )
    (net (code "56") (name "Net-(JP56-P$1)") (class "Default")
      (node (ref "JMP-ID") (pin "2") (pinfunction "2_2") (pintype "passive"))
      (node (ref "JP56") (pin "1") (pinfunction "P$1_1") (pintype "bidirectional"))
      (node (ref "USB") (pin "ID") (pinfunction "ID_ID") (pintype "bidirectional"))
    )
    (net (code "57") (name "Net-(JP57-P$1)") (class "Default")
      (node (ref "JP57") (pin "1") (pinfunction "P$1_1") (pintype "bidirectional"))
      (node (ref "JP66") (pin "4") (pinfunction "4_4") (pintype "passive"))
      (node (ref "U1") (pin "28") (pinfunction "BOOT1(PB2)_28") (pintype "input"))
    )
    (net (code "58") (name "Net-(JP58-P$1)") (class "Default")
      (node (ref "JP58") (pin "1") (pinfunction "P$1_1") (pintype "bidirectional"))
      (node (ref "R5") (pin "2") (pinfunction "2_2") (pintype "passive"))
      (node (ref "U1") (pin "44") (pinfunction "USB_DM(PA11)_44") (pintype "bidirectional"))
    )
    (net (code "59") (name "Net-(JP64-P$1)") (class "Default")
      (node (ref "JMP-VBUS") (pin "2") (pinfunction "2_2") (pintype "passive"))
      (node (ref "JP64") (pin "1") (pinfunction "P$1_1") (pintype "bidirectional"))
      (node (ref "U1") (pin "42") (pinfunction "VBUS(PA9)_42") (pintype "bidirectional"))
    )
    (net (code "60") (name "Net-(LED1-PadC)") (class "Default")
      (node (ref "LED1") (pin "C") (pinfunction "C_C") (pintype "passive"))
      (node (ref "R3") (pin "2") (pinfunction "2_2") (pintype "passive"))
    )
    (net (code "61") (name "Net-(Q1-B)") (class "Default")
      (node (ref "Q1") (pin "1") (pinfunction "B_1") (pintype "passive"))
      (node (ref "R7") (pin "2") (pinfunction "2_2") (pintype "passive"))
      (node (ref "R8") (pin "1") (pinfunction "1_1") (pintype "passive"))
    )
    (net (code "62") (name "Net-(Q1-C)") (class "Default")
      (node (ref "Q1") (pin "3") (pinfunction "C_3") (pintype "passive"))
      (node (ref "R6") (pin "2") (pinfunction "2_2") (pintype "passive"))
    )
    (net (code "63") (name "Net-(U1-BOOT0)") (class "Default")
      (node (ref "JP66") (pin "3") (pinfunction "3_3") (pintype "passive"))
      (node (ref "U1") (pin "60") (pinfunction "BOOT0_60") (pintype "input"))
    )
    (net (code "64") (name "Net-(U1-OSC_IN(PH0))") (class "Default")
      (node (ref "C12") (pin "1") (pinfunction "1_1") (pintype "passive"))
      (node (ref "U1") (pin "5") (pinfunction "OSC_IN(PH0)_5") (pintype "bidirectional"))
      (node (ref "Y1") (pin "3") (pinfunction "2_3") (pintype "passive"))
    )
    (net (code "65") (name "Net-(U1-OSC_OUT(PH1))") (class "Default")
      (node (ref "C13") (pin "1") (pinfunction "1_1") (pintype "passive"))
      (node (ref "U1") (pin "6") (pinfunction "OSC_OUT(PH1)_6") (pintype "bidirectional"))
      (node (ref "Y1") (pin "1") (pinfunction "1_1") (pintype "passive"))
    )
    (net (code "66") (name "Net-(U1-VCAP_1)") (class "Default")
      (node (ref "C7") (pin "1") (pinfunction "1_1") (pintype "passive"))
      (node (ref "U1") (pin "31") (pinfunction "VCAP_1_31") (pintype "bidirectional"))
    )
    (net (code "67") (name "Net-(U1-VCAP_2)") (class "Default")
      (node (ref "C8") (pin "1") (pinfunction "1_1") (pintype "passive"))
      (node (ref "U1") (pin "47") (pinfunction "VCAP_2_47") (pintype "bidirectional"))
    )
    (net (code "68") (name "Net-(U1-VDDA)") (class "Default")
      (node (ref "C6") (pin "1") (pinfunction "1_1") (pintype "passive"))
      (node (ref "L1") (pin "1") (pinfunction "1_1") (pintype "passive"))
      (node (ref "U1") (pin "13") (pinfunction "VDDA_13") (pintype "power_in"))
    )
    (net (code "69") (name "Net-(U2-IO1)") (class "Default")
      (node (ref "R4") (pin "1") (pinfunction "1_1") (pintype "passive"))
      (node (ref "U2") (pin "2") (pinfunction "IO1_2") (pintype "bidirectional"))
      (node (ref "USB") (pin "D+") (pinfunction "D+_D+") (pintype "bidirectional"))
    )
    (net (code "70") (name "Net-(U2-IO2)") (class "Default")
      (node (ref "R5") (pin "1") (pinfunction "1_1") (pintype "passive"))
      (node (ref "U2") (pin "3") (pinfunction "IO2_3") (pintype "bidirectional"))
      (node (ref "USB") (pin "D-") (pinfunction "D-_D-") (pintype "bidirectional"))
    )
    (net (code "71") (name "Net-(U2-VCC)") (class "Default")
      (node (ref "C17") (pin "1") (pinfunction "1_1") (pintype "passive"))
      (node (ref "L2") (pin "1") (pinfunction "1_1") (pintype "passive"))
      (node (ref "U2") (pin "4") (pinfunction "VCC_4") (pintype "bidirectional"))
      (node (ref "USB") (pin "VBUS") (pinfunction "VBUS_VBUS") (pintype "bidirectional"))
    )
  )
)
